# LDBiasDriver_CC.net
KiCad netlist of a schematic drawn in EAGLE
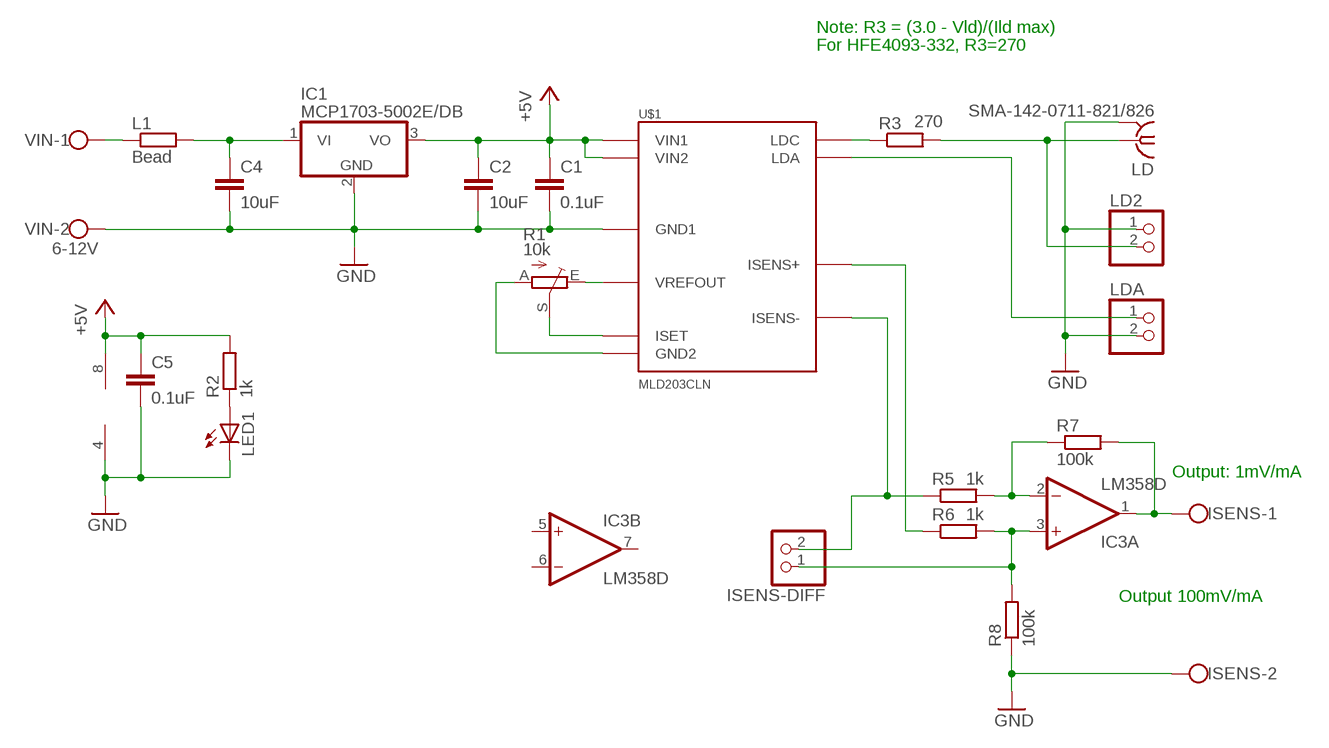
[diagram p0: schematic, sheet 1]

(export (version "E")
  (design (tool "Eeschema 10.0.6"))
  (components
    (comp (ref "C1")
      (value "0.1uF")
      (footprint "eagle-import:C0805")
      (libsource (lib "eagle-import") (part "C-EUC0805"))
    )
    (comp (ref "C2")
      (value "10uF")
      (footprint "eagle-import:C0805")
      (libsource (lib "eagle-import") (part "C-EUC0805"))
    )
    (comp (ref "C4")
      (value "10uF")
      (footprint "eagle-import:C0805")
      (libsource (lib "eagle-import") (part "C-EUC0805"))
    )
    (comp (ref "C5")
      (value "0.1uF")
      (footprint "eagle-import:C0805")
      (libsource (lib "eagle-import") (part "C-EUC0805"))
    )
    (comp (ref "IC1")
      (value "MCP1703-5002E/DB")
      (footprint "eagle-import:SOT223")
      (libsource (lib "eagle-import") (part "MCP1703DB"))
    )
    (comp (ref "IC3")
      (value "LM358D")
      (footprint "eagle-import:SO08")
      (libsource (lib "eagle-import") (part "LM358D"))
    )
    (comp (ref "ISENS")
      (value "W237-102")
      (footprint "eagle-import:W237-102")
      (fields (field (name "MPN") "237-102"))
      (libsource (lib "eagle-import") (part "W237-102"))
    )
    (comp (ref "ISENS-DIFF")
      (value "PINHD-1X2")
      (footprint "eagle-import:1X02")
      (libsource (lib "eagle-import") (part "PINHD-1X2"))
    )
    (comp (ref "L1")
      (value "Bead")
      (footprint "eagle-import:R0805")
      (libsource (lib "eagle-import") (part "R-EU_R0805"))
    )
    (comp (ref "LD")
      (value "SMA-142-0711-821/826")
      (footprint "eagle-import:J502-ND-142-0711-821_826")
      (fields (field (name "MF") "JOHNSON COMPONENTS") (field (name "MPN") "142-0711-821"))
      (libsource (lib "eagle-import") (part "SMA-142-0711-821/826"))
    )
    (comp (ref "LD2")
      (value "PINHD-1X2")
      (footprint "eagle-import:1X02")
      (libsource (lib "eagle-import") (part "PINHD-1X2"))
    )
    (comp (ref "LDA")
      (value "PINHD-1X2")
      (footprint "eagle-import:1X02")
      (libsource (lib "eagle-import") (part "PINHD-1X2"))
    )
    (comp (ref "LED1")
      (value "LEDCHIPLED_1206")
      (footprint "eagle-import:CHIPLED_1206")
      (libsource (lib "eagle-import") (part "LEDCHIPLED_1206"))
    )
    (comp (ref "R1")
      (value "10k")
      (footprint "eagle-import:RJ9W")
      (libsource (lib "eagle-import") (part "TRIM_EU-RJ9W"))
    )
    (comp (ref "R2")
      (value "1k")
      (footprint "eagle-import:R0805")
      (libsource (lib "eagle-import") (part "R-EU_R0805"))
    )
    (comp (ref "R3")
      (value "270")
      (footprint "eagle-import:R0805")
      (libsource (lib "eagle-import") (part "R-EU_R0805"))
    )
    (comp (ref "R5")
      (value "1k")
      (footprint "eagle-import:R0805")
      (libsource (lib "eagle-import") (part "R-EU_R0805"))
    )
    (comp (ref "R6")
      (value "1k")
      (footprint "eagle-import:R0805")
      (libsource (lib "eagle-import") (part "R-EU_R0805"))
    )
    (comp (ref "R7")
      (value "100k")
      (footprint "eagle-import:R0805")
      (libsource (lib "eagle-import") (part "R-EU_R0805"))
    )
    (comp (ref "R8")
      (value "100k")
      (footprint "eagle-import:R0805")
      (libsource (lib "eagle-import") (part "R-EU_R0805"))
    )
    (comp (ref "U$1")
      (value "MLD203CLN")
      (footprint "eagle-import:MLD203")
      (libsource (lib "eagle-import") (part "MLD203CLN"))
    )
    (comp (ref "VIN")
      (value "6-12V")
      (footprint "eagle-import:W237-102")
      (fields (field (name "MPN") "237-102"))
      (libsource (lib "eagle-import") (part "W237-102"))
    )
  )
  (nets
    (net (code "1") (name "+5V") (class "Default")
      (node (ref "C1") (pin "1") (pinfunction "1_1") (pintype "passive"))
      (node (ref "C2") (pin "1") (pinfunction "1_1") (pintype "passive"))
      (node (ref "C5") (pin "1") (pinfunction "1_1") (pintype "passive"))
      (node (ref "IC1") (pin "3") (pinfunction "VO_3") (pintype "passive"))
      (node (ref "IC3") (pin "8") (pinfunction "V+_8") (pintype "power_in"))
      (node (ref "R2") (pin "2") (pinfunction "2_2") (pintype "passive"))
      (node (ref "U$1") (pin "P$1") (pinfunction "VIN1_P$1") (pintype "power_in"))
      (node (ref "U$1") (pin "P$2") (pinfunction "VIN2_P$2") (pintype "power_in"))
    )
    (net (code "2") (name "GND") (class "Default")
      (node (ref "C1") (pin "2") (pinfunction "2_2") (pintype "passive"))
      (node (ref "C2") (pin "2") (pinfunction "2_2") (pintype "passive"))
      (node (ref "C4") (pin "2") (pinfunction "2_2") (pintype "passive"))
      (node (ref "C5") (pin "2") (pinfunction "2_2") (pintype "passive"))
      (node (ref "IC1") (pin "2") (pinfunction "GND_2") (pintype "passive"))
      (node (ref "IC3") (pin "4") (pinfunction "V-_4") (pintype "power_in"))
      (node (ref "ISENS") (pin "2") (pinfunction "KL_2") (pintype "passive"))
      (node (ref "LD") (pin "G@1") (pinfunction "2_G@1") (pintype "passive"))
      (node (ref "LD") (pin "G@2") (pinfunction "2_G@2") (pintype "passive"))
      (node (ref "LD") (pin "G@3") (pinfunction "2_G@3") (pintype "passive"))
      (node (ref "LD") (pin "G@4") (pinfunction "2_G@4") (pintype "passive"))
      (node (ref "LD2") (pin "1") (pinfunction "1_1") (pintype "passive"))
      (node (ref "LDA") (pin "2") (pinfunction "2_2") (pintype "passive"))
      (node (ref "LED1") (pin "C") (pinfunction "C_C") (pintype "passive"))
      (node (ref "R8") (pin "1") (pinfunction "1_1") (pintype "passive"))
      (node (ref "U$1") (pin "P$3") (pinfunction "GND1_P$3") (pintype "power_in"))
      (node (ref "VIN") (pin "2") (pinfunction "KL_2") (pintype "passive"))
    )
    (net (code "3") (name "Net-(IC1-VI)") (class "Default")
      (node (ref "C4") (pin "1") (pinfunction "1_1") (pintype "passive"))
      (node (ref "IC1") (pin "1") (pinfunction "VI_1") (pintype "input"))
      (node (ref "L1") (pin "2") (pinfunction "2_2") (pintype "passive"))
    )
    (net (code "4") (name "Net-(IC3A-+IN)") (class "Default")
      (node (ref "IC3") (pin "3") (pinfunction "+IN_3") (pintype "input"))
      (node (ref "ISENS-DIFF") (pin "1") (pinfunction "1_1") (pintype "passive"))
      (node (ref "R6") (pin "2") (pinfunction "2_2") (pintype "passive"))
      (node (ref "R8") (pin "2") (pinfunction "2_2") (pintype "passive"))
    )
    (net (code "5") (name "Net-(IC3A--IN)") (class "Default")
      (node (ref "IC3") (pin "2") (pinfunction "-IN_2") (pintype "input"))
      (node (ref "R5") (pin "2") (pinfunction "2_2") (pintype "passive"))
      (node (ref "R7") (pin "1") (pinfunction "1_1") (pintype "passive"))
    )
    (net (code "6") (name "Net-(IC3A-OUT)") (class "Default")
      (node (ref "IC3") (pin "1") (pinfunction "OUT_1") (pintype "output"))
      (node (ref "ISENS") (pin "1") (pinfunction "KL_1") (pintype "passive"))
      (node (ref "R7") (pin "2") (pinfunction "2_2") (pintype "passive"))
    )
    (net (code "7") (name "Net-(LD-Pad1)") (class "Default")
      (node (ref "LD") (pin "1") (pinfunction "1_1") (pintype "passive"))
      (node (ref "LD2") (pin "2") (pinfunction "2_2") (pintype "passive"))
      (node (ref "R3") (pin "2") (pinfunction "2_2") (pintype "passive"))
    )
    (net (code "8") (name "Net-(LED1-PadA)") (class "Default")
      (node (ref "LED1") (pin "A") (pinfunction "A_A") (pintype "passive"))
      (node (ref "R2") (pin "1") (pinfunction "1_1") (pintype "passive"))
    )
    (net (code "9") (name "Net-(U$1-GND2)") (class "Default")
      (node (ref "R1") (pin "A") (pinfunction "A_A") (pintype "passive"))
      (node (ref "U$1") (pin "P$4") (pinfunction "GND2_P$4") (pintype "power_in"))
    )
    (net (code "10") (name "Net-(U$1-ISENS+)") (class "Default")
      (node (ref "R6") (pin "1") (pinfunction "1_1") (pintype "passive"))
      (node (ref "U$1") (pin "P$12") (pinfunction "ISENS+_P$12") (pintype "bidirectional"))
    )
    (net (code "11") (name "Net-(U$1-ISENS-)") (class "Default")
      (node (ref "ISENS-DIFF") (pin "2") (pinfunction "2_2") (pintype "passive"))
      (node (ref "R5") (pin "1") (pinfunction "1_1") (pintype "passive"))
      (node (ref "U$1") (pin "P$13") (pinfunction "ISENS-_P$13") (pintype "bidirectional"))
    )
    (net (code "12") (name "Net-(U$1-ISET)") (class "Default")
      (node (ref "R1") (pin "S") (pinfunction "S_S") (pintype "passive"))
      (node (ref "U$1") (pin "P$6") (pinfunction "ISET_P$6") (pintype "bidirectional"))
    )
    (net (code "13") (name "Net-(U$1-LDA)") (class "Default")
      (node (ref "LDA") (pin "1") (pinfunction "1_1") (pintype "passive"))
      (node (ref "U$1") (pin "P$14") (pinfunction "LDA_P$14") (pintype "bidirectional"))
    )
    (net (code "14") (name "Net-(U$1-LDC)") (class "Default")
      (node (ref "R3") (pin "1") (pinfunction "1_1") (pintype "passive"))
      (node (ref "U$1") (pin "P$11") (pinfunction "LDC_P$11") (pintype "bidirectional"))
    )
    (net (code "15") (name "Net-(U$1-VREFOUT)") (class "Default")
      (node (ref "R1") (pin "E") (pinfunction "E_E") (pintype "passive"))
      (node (ref "U$1") (pin "P$5") (pinfunction "VREFOUT_P$5") (pintype "bidirectional"))
    )
    (net (code "16") (name "Net-(VINA-KL)") (class "Default")
      (node (ref "L1") (pin "1") (pinfunction "1_1") (pintype "passive"))
      (node (ref "VIN") (pin "1") (pinfunction "KL_1") (pintype "passive"))
    )
    (net (code "17") (name "unconnected-(IC3B-+IN-Pad5)") (class "Default")
      (node (ref "IC3") (pin "5") (pinfunction "+IN_5") (pintype "input"))
    )
    (net (code "18") (name "unconnected-(IC3B--IN-Pad6)") (class "Default")
      (node (ref "IC3") (pin "6") (pinfunction "-IN_6") (pintype "input"))
    )
    (net (code "19") (name "unconnected-(IC3B-OUT-Pad7)") (class "Default")
      (node (ref "IC3") (pin "7") (pinfunction "OUT_7") (pintype "output"))
    )
  )
)
